# touch_pot_v13.net
KiCad netlist of a schematic drawn in EAGLE
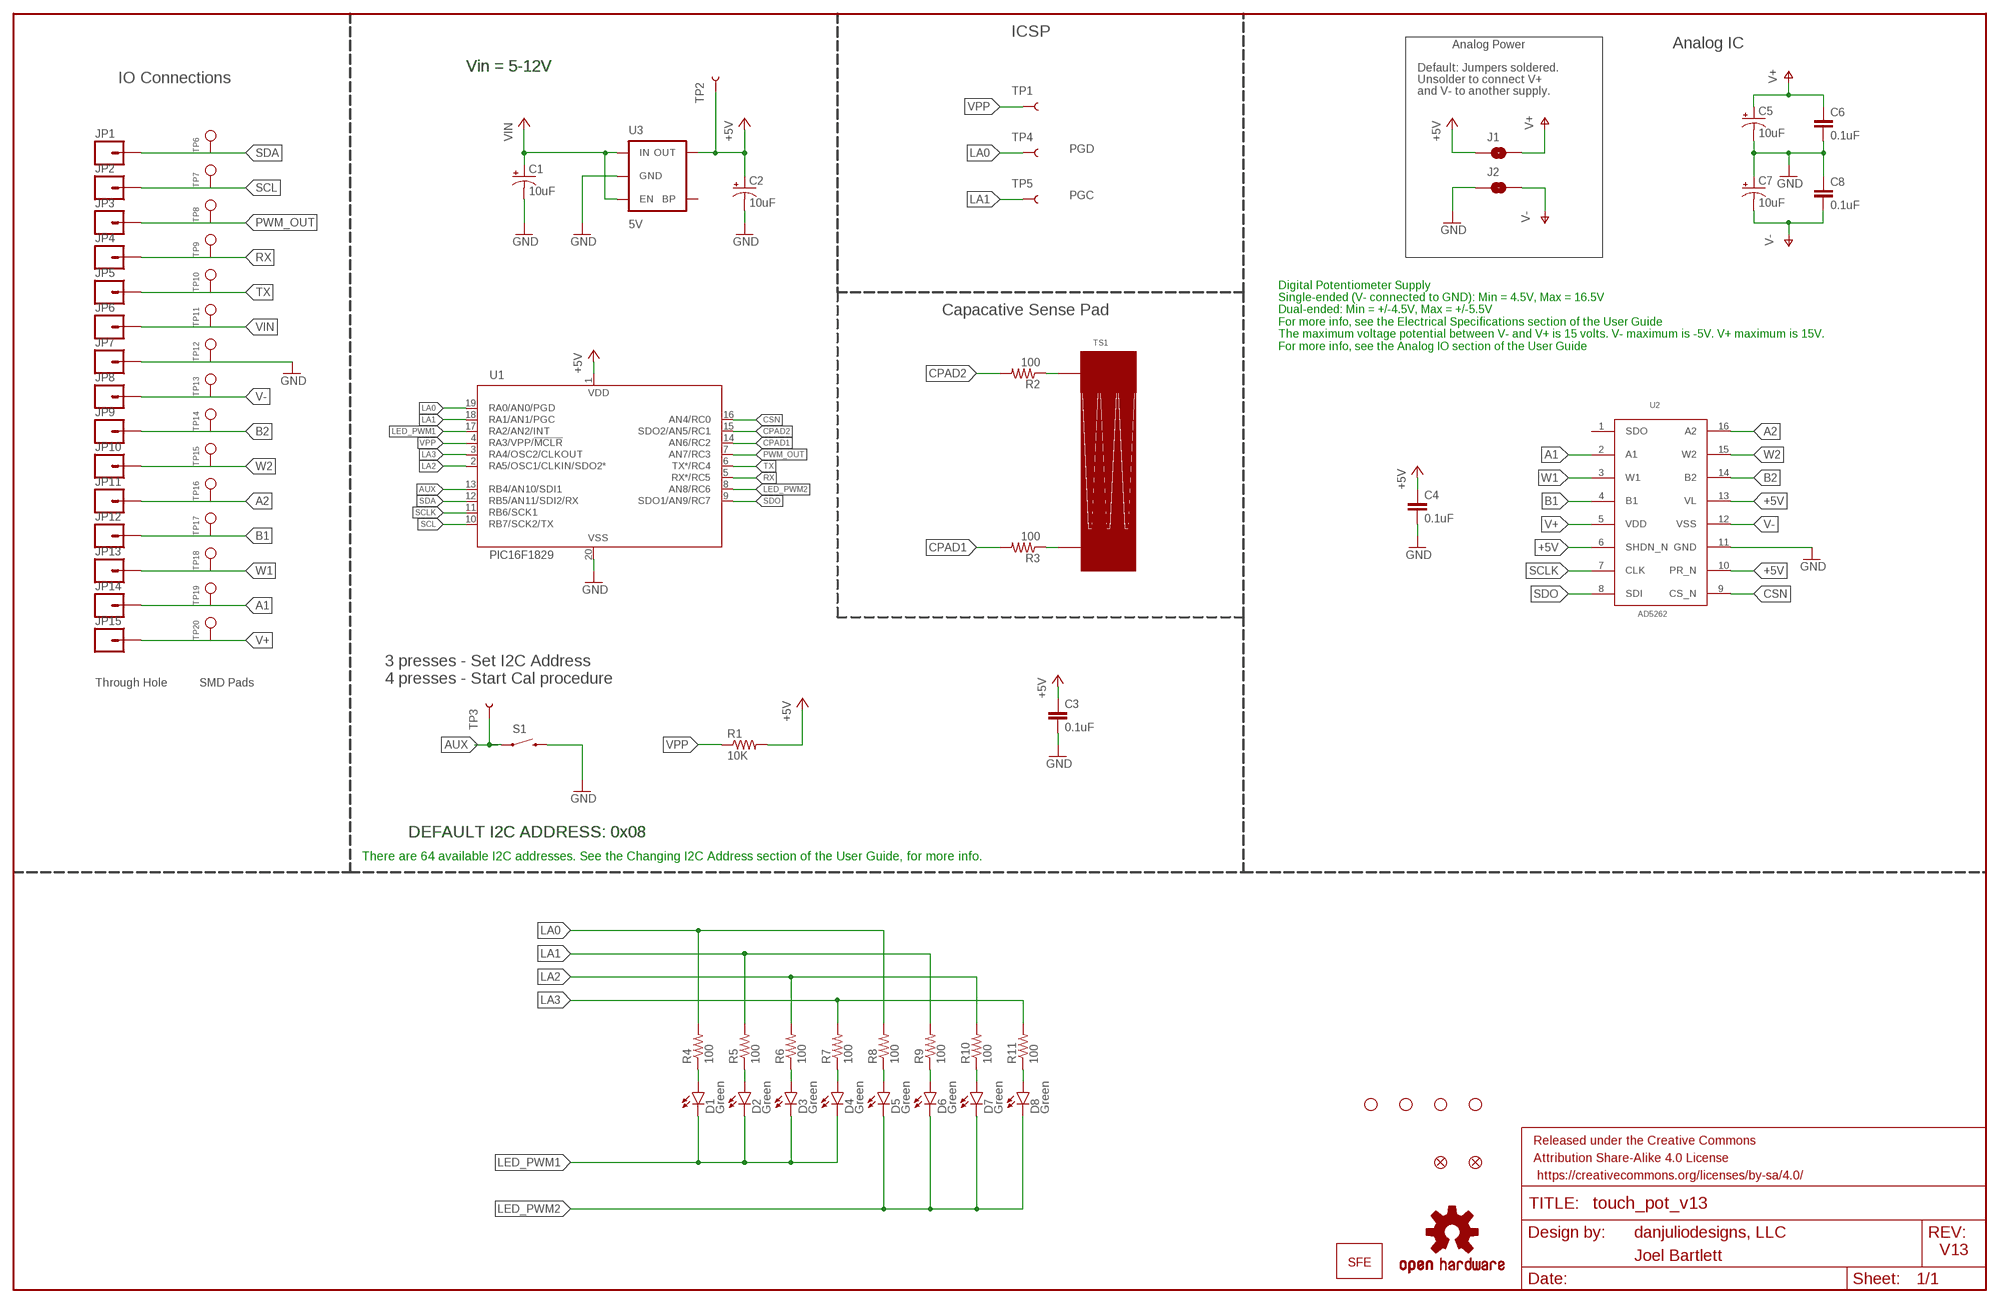
[diagram p0: schematic, sheet 1]

(export (version "E")
  (design (tool "Eeschema 10.0.6"))
  (components
    (comp (ref "C1")
      (value "10uF")
      (footprint "eagle-import:EIA3216")
      (libsource (lib "eagle-import") (part "10UF-16V-10%(TANT)"))
    )
    (comp (ref "C2")
      (value "10uF")
      (footprint "eagle-import:EIA3216")
      (libsource (lib "eagle-import") (part "10UF-16V-10%(TANT)"))
    )
    (comp (ref "C3")
      (value "0.1uF")
      (footprint "eagle-import:0603-CAP")
      (libsource (lib "eagle-import") (part "0.1UF-25V(+80/-20%)(0603)"))
    )
    (comp (ref "C4")
      (value "0.1uF")
      (footprint "eagle-import:0603-CAP")
      (libsource (lib "eagle-import") (part "0.1UF-25V(+80/-20%)(0603)"))
    )
    (comp (ref "C5")
      (value "10uF")
      (footprint "eagle-import:EIA3216")
      (libsource (lib "eagle-import") (part "10UF-16V-10%(TANT)"))
    )
    (comp (ref "C6")
      (value "0.1uF")
      (footprint "eagle-import:0603-CAP")
      (libsource (lib "eagle-import") (part "0.1UF-25V(+80/-20%)(0603)"))
    )
    (comp (ref "C7")
      (value "10uF")
      (footprint "eagle-import:EIA3216")
      (libsource (lib "eagle-import") (part "10UF-16V-10%(TANT)"))
    )
    (comp (ref "C8")
      (value "0.1uF")
      (footprint "eagle-import:0603-CAP")
      (libsource (lib "eagle-import") (part "0.1UF-25V(+80/-20%)(0603)"))
    )
    (comp (ref "D1")
      (value "Green")
      (footprint "eagle-import:LED-1206-BOTTOM")
      (libsource (lib "eagle-import") (part "LED-GREEN1206-BOTTOM"))
    )
    (comp (ref "D2")
      (value "Green")
      (footprint "eagle-import:LED-1206-BOTTOM")
      (libsource (lib "eagle-import") (part "LED-GREEN1206-BOTTOM"))
    )
    (comp (ref "D3")
      (value "Green")
      (footprint "eagle-import:LED-1206-BOTTOM")
      (libsource (lib "eagle-import") (part "LED-GREEN1206-BOTTOM"))
    )
    (comp (ref "D4")
      (value "Green")
      (footprint "eagle-import:LED-1206-BOTTOM")
      (libsource (lib "eagle-import") (part "LED-GREEN1206-BOTTOM"))
    )
    (comp (ref "D5")
      (value "Green")
      (footprint "eagle-import:LED-1206-BOTTOM")
      (libsource (lib "eagle-import") (part "LED-GREEN1206-BOTTOM"))
    )
    (comp (ref "D6")
      (value "Green")
      (footprint "eagle-import:LED-1206-BOTTOM")
      (libsource (lib "eagle-import") (part "LED-GREEN1206-BOTTOM"))
    )
    (comp (ref "D7")
      (value "Green")
      (footprint "eagle-import:LED-1206-BOTTOM")
      (libsource (lib "eagle-import") (part "LED-GREEN1206-BOTTOM"))
    )
    (comp (ref "D8")
      (value "Green")
      (footprint "eagle-import:LED-1206-BOTTOM")
      (libsource (lib "eagle-import") (part "LED-GREEN1206-BOTTOM"))
    )
    (comp (ref "FID1")
      (value "FIDUCIAL1X2")
      (footprint "eagle-import:FIDUCIAL-1X2")
      (libsource (lib "eagle-import") (part "FIDUCIAL1X2"))
    )
    (comp (ref "FID2")
      (value "FIDUCIAL1X2")
      (footprint "eagle-import:FIDUCIAL-1X2")
      (libsource (lib "eagle-import") (part "FIDUCIAL1X2"))
    )
    (comp (ref "FRAME3")
      (value "FRAME-LEDGER")
      (footprint "eagle-import:CREATIVE_COMMONS")
      (libsource (lib "eagle-import") (part "FRAME-LEDGER"))
    )
    (comp (ref "J1")
      (value "SJCLOSED")
      (footprint "eagle-import:SJ_2S")
      (libsource (lib "eagle-import") (part "SJCLOSED"))
    )
    (comp (ref "J2")
      (value "SJCLOSED")
      (footprint "eagle-import:SJ_2S")
      (libsource (lib "eagle-import") (part "SJCLOSED"))
    )
    (comp (ref "JP1")
      (value "M01SMDNS")
      (footprint "eagle-import:1X01NS")
      (libsource (lib "eagle-import") (part "M01SMDNS"))
    )
    (comp (ref "JP2")
      (value "M01SMDNS")
      (footprint "eagle-import:1X01NS")
      (libsource (lib "eagle-import") (part "M01SMDNS"))
    )
    (comp (ref "JP3")
      (value "M01SMDNS")
      (footprint "eagle-import:1X01NS")
      (libsource (lib "eagle-import") (part "M01SMDNS"))
    )
    (comp (ref "JP4")
      (value "M01SMDNS")
      (footprint "eagle-import:1X01NS")
      (libsource (lib "eagle-import") (part "M01SMDNS"))
    )
    (comp (ref "JP5")
      (value "M01SMDNS")
      (footprint "eagle-import:1X01NS")
      (libsource (lib "eagle-import") (part "M01SMDNS"))
    )
    (comp (ref "JP6")
      (value "M01SMDNS")
      (footprint "eagle-import:1X01NS")
      (libsource (lib "eagle-import") (part "M01SMDNS"))
    )
    (comp (ref "JP7")
      (value "M01SMDNS")
      (footprint "eagle-import:1X01NS")
      (libsource (lib "eagle-import") (part "M01SMDNS"))
    )
    (comp (ref "JP8")
      (value "M01SMDNS")
      (footprint "eagle-import:1X01NS")
      (libsource (lib "eagle-import") (part "M01SMDNS"))
    )
    (comp (ref "JP9")
      (value "M01SMDNS")
      (footprint "eagle-import:1X01NS")
      (libsource (lib "eagle-import") (part "M01SMDNS"))
    )
    (comp (ref "JP10")
      (value "M01SMDNS")
      (footprint "eagle-import:1X01NS")
      (libsource (lib "eagle-import") (part "M01SMDNS"))
    )
    (comp (ref "JP11")
      (value "M01SMDNS")
      (footprint "eagle-import:1X01NS")
      (libsource (lib "eagle-import") (part "M01SMDNS"))
    )
    (comp (ref "JP12")
      (value "M01SMDNS")
      (footprint "eagle-import:1X01NS")
      (libsource (lib "eagle-import") (part "M01SMDNS"))
    )
    (comp (ref "JP13")
      (value "M01SMDNS")
      (footprint "eagle-import:1X01NS")
      (libsource (lib "eagle-import") (part "M01SMDNS"))
    )
    (comp (ref "JP14")
      (value "M01SMDNS")
      (footprint "eagle-import:1X01NS")
      (libsource (lib "eagle-import") (part "M01SMDNS"))
    )
    (comp (ref "JP15")
      (value "M01SMDNS")
      (footprint "eagle-import:1X01NS")
      (libsource (lib "eagle-import") (part "M01SMDNS"))
    )
    (comp (ref "R1")
      (value "10K")
      (footprint "eagle-import:0603-RES")
      (libsource (lib "eagle-import") (part "10KOHM-1/10W-1%(0603)0603"))
    )
    (comp (ref "R2")
      (value "100")
      (footprint "eagle-import:0603-RES")
      (libsource (lib "eagle-import") (part "100OHM-1/10W-1%(0603)"))
    )
    (comp (ref "R3")
      (value "100")
      (footprint "eagle-import:0603-RES")
      (libsource (lib "eagle-import") (part "100OHM-1/10W-1%(0603)"))
    )
    (comp (ref "R4")
      (value "100")
      (footprint "eagle-import:0603-RES")
      (libsource (lib "eagle-import") (part "100OHM-1/10W-1%(0603)"))
    )
    (comp (ref "R5")
      (value "100")
      (footprint "eagle-import:0603-RES")
      (libsource (lib "eagle-import") (part "100OHM-1/10W-1%(0603)"))
    )
    (comp (ref "R6")
      (value "100")
      (footprint "eagle-import:0603-RES")
      (libsource (lib "eagle-import") (part "100OHM-1/10W-1%(0603)"))
    )
    (comp (ref "R7")
      (value "100")
      (footprint "eagle-import:0603-RES")
      (libsource (lib "eagle-import") (part "100OHM-1/10W-1%(0603)"))
    )
    (comp (ref "R8")
      (value "100")
      (footprint "eagle-import:0603-RES")
      (libsource (lib "eagle-import") (part "100OHM-1/10W-1%(0603)"))
    )
    (comp (ref "R9")
      (value "100")
      (footprint "eagle-import:0603-RES")
      (libsource (lib "eagle-import") (part "100OHM-1/10W-1%(0603)"))
    )
    (comp (ref "R10")
      (value "100")
      (footprint "eagle-import:0603-RES")
      (libsource (lib "eagle-import") (part "100OHM-1/10W-1%(0603)"))
    )
    (comp (ref "R11")
      (value "100")
      (footprint "eagle-import:0603-RES")
      (libsource (lib "eagle-import") (part "100OHM-1/10W-1%(0603)"))
    )
    (comp (ref "S1")
      (value "SWITCH-MOMENTARY-2SMD")
      (footprint "eagle-import:TACTILE-SWITCH-SMD")
      (libsource (lib "eagle-import") (part "SWITCH-MOMENTARY-2SMD"))
    )
    (comp (ref "STANDOFF1")
      (value "STAND-OFFTIGHT")
      (footprint "eagle-import:STAND-OFF-TIGHT")
      (libsource (lib "eagle-import") (part "STAND-OFFTIGHT"))
    )
    (comp (ref "STANDOFF2")
      (value "STAND-OFFTIGHT")
      (footprint "eagle-import:STAND-OFF-TIGHT")
      (libsource (lib "eagle-import") (part "STAND-OFFTIGHT"))
    )
    (comp (ref "STANDOFF3")
      (value "STAND-OFFTIGHT")
      (footprint "eagle-import:STAND-OFF-TIGHT")
      (libsource (lib "eagle-import") (part "STAND-OFFTIGHT"))
    )
    (comp (ref "STANDOFF4")
      (value "STAND-OFFTIGHT")
      (footprint "eagle-import:STAND-OFF-TIGHT")
      (libsource (lib "eagle-import") (part "STAND-OFFTIGHT"))
    )
    (comp (ref "TP1")
      (value "TEST-POINT3X4")
      (footprint "eagle-import:PAD.03X.04")
      (libsource (lib "eagle-import") (part "TEST-POINT3X4"))
    )
    (comp (ref "TP2")
      (value "TEST-POINT3X4")
      (footprint "eagle-import:PAD.03X.04")
      (libsource (lib "eagle-import") (part "TEST-POINT3X4"))
    )
    (comp (ref "TP3")
      (value "TEST-POINT3X4")
      (footprint "eagle-import:PAD.03X.04")
      (libsource (lib "eagle-import") (part "TEST-POINT3X4"))
    )
    (comp (ref "TP4")
      (value "TEST-POINT3X4")
      (footprint "eagle-import:PAD.03X.04")
      (libsource (lib "eagle-import") (part "TEST-POINT3X4"))
    )
    (comp (ref "TP5")
      (value "TEST-POINT3X4")
      (footprint "eagle-import:PAD.03X.04")
      (libsource (lib "eagle-import") (part "TEST-POINT3X4"))
    )
    (comp (ref "TP6")
      (value "SINGLE_PADSMD")
      (footprint "eagle-import:2MM_SMD_PAD")
      (libsource (lib "eagle-import") (part "SINGLE_PADSMD"))
    )
    (comp (ref "TP7")
      (value "SINGLE_PADSMD")
      (footprint "eagle-import:2MM_SMD_PAD")
      (libsource (lib "eagle-import") (part "SINGLE_PADSMD"))
    )
    (comp (ref "TP8")
      (value "SINGLE_PADSMD")
      (footprint "eagle-import:2MM_SMD_PAD")
      (libsource (lib "eagle-import") (part "SINGLE_PADSMD"))
    )
    (comp (ref "TP9")
      (value "SINGLE_PADSMD")
      (footprint "eagle-import:2MM_SMD_PAD")
      (libsource (lib "eagle-import") (part "SINGLE_PADSMD"))
    )
    (comp (ref "TP10")
      (value "SINGLE_PADSMD")
      (footprint "eagle-import:2MM_SMD_PAD")
      (libsource (lib "eagle-import") (part "SINGLE_PADSMD"))
    )
    (comp (ref "TP11")
      (value "SINGLE_PADSMD")
      (footprint "eagle-import:2MM_SMD_PAD")
      (libsource (lib "eagle-import") (part "SINGLE_PADSMD"))
    )
    (comp (ref "TP12")
      (value "SINGLE_PADSMD")
      (footprint "eagle-import:2MM_SMD_PAD")
      (libsource (lib "eagle-import") (part "SINGLE_PADSMD"))
    )
    (comp (ref "TP13")
      (value "SINGLE_PADSMD")
      (footprint "eagle-import:2MM_SMD_PAD")
      (libsource (lib "eagle-import") (part "SINGLE_PADSMD"))
    )
    (comp (ref "TP14")
      (value "SINGLE_PADSMD")
      (footprint "eagle-import:2MM_SMD_PAD")
      (libsource (lib "eagle-import") (part "SINGLE_PADSMD"))
    )
    (comp (ref "TP15")
      (value "SINGLE_PADSMD")
      (footprint "eagle-import:2MM_SMD_PAD")
      (libsource (lib "eagle-import") (part "SINGLE_PADSMD"))
    )
    (comp (ref "TP16")
      (value "SINGLE_PADSMD")
      (footprint "eagle-import:2MM_SMD_PAD")
      (libsource (lib "eagle-import") (part "SINGLE_PADSMD"))
    )
    (comp (ref "TP17")
      (value "SINGLE_PADSMD")
      (footprint "eagle-import:2MM_SMD_PAD")
      (libsource (lib "eagle-import") (part "SINGLE_PADSMD"))
    )
    (comp (ref "TP18")
      (value "SINGLE_PADSMD")
      (footprint "eagle-import:2MM_SMD_PAD")
      (libsource (lib "eagle-import") (part "SINGLE_PADSMD"))
    )
    (comp (ref "TP19")
      (value "SINGLE_PADSMD")
      (footprint "eagle-import:2MM_SMD_PAD")
      (libsource (lib "eagle-import") (part "SINGLE_PADSMD"))
    )
    (comp (ref "TP20")
      (value "SINGLE_PADSMD")
      (footprint "eagle-import:2MM_SMD_PAD")
      (libsource (lib "eagle-import") (part "SINGLE_PADSMD"))
    )
    (comp (ref "TS1")
      (value "2CH_LINEAR_TOUCH")
      (footprint "eagle-import:2CH_48MM_LINEAR_TOUCH")
      (libsource (lib "eagle-import") (part "2CH_LINEAR_TOUCH"))
    )
    (comp (ref "U$4")
      (value "OSHW-LOGOM")
      (footprint "eagle-import:OSHW-LOGO-M")
      (libsource (lib "eagle-import") (part "OSHW-LOGOM"))
    )
    (comp (ref "U$5")
      (value "SFE_LOGO_NAME_WEB")
      (footprint "eagle-import:SFE-NEW-WEBLOGO")
      (libsource (lib "eagle-import") (part "SFE_LOGO_NAME_WEB"))
    )
    (comp (ref "U1")
      (value "PIC16F1829")
      (footprint "eagle-import:SSOP20")
      (libsource (lib "eagle-import") (part "PIC16F1829"))
    )
    (comp (ref "U2")
      (value "AD5262")
      (footprint "eagle-import:SSOP16")
      (libsource (lib "eagle-import") (part "AD5262"))
    )
    (comp (ref "U3")
      (value "5V")
      (footprint "eagle-import:SOT23-5")
      (libsource (lib "eagle-import") (part "V_REG_MIC52055V"))
    )
  )
  (nets
    (net (code "1") (name "+5V") (class "Default")
      (node (ref "C2") (pin "A") (pinfunction "+_A") (pintype "passive"))
      (node (ref "C3") (pin "1") (pinfunction "1_1") (pintype "passive"))
      (node (ref "C4") (pin "1") (pinfunction "1_1") (pintype "passive"))
      (node (ref "J1") (pin "1") (pinfunction "1_1") (pintype "passive"))
      (node (ref "R1") (pin "2") (pinfunction "2_2") (pintype "passive"))
      (node (ref "TP2") (pin "P$1") (pinfunction "1_P$1") (pintype "bidirectional"))
      (node (ref "U1") (pin "1") (pinfunction "VDD_1") (pintype "power_in"))
      (node (ref "U2") (pin "10") (pinfunction "PR_N_10") (pintype "input"))
      (node (ref "U2") (pin "13") (pinfunction "VL_13") (pintype "power_in"))
      (node (ref "U2") (pin "6") (pinfunction "SHDN_N_6") (pintype "input"))
      (node (ref "U3") (pin "5") (pinfunction "OUT_5") (pintype "passive"))
    )
    (net (code "2") (name "A1") (class "Default")
      (node (ref "JP14") (pin "1") (pinfunction "1_1") (pintype "passive"))
      (node (ref "TP19") (pin "P$1") (pinfunction "P$1_P$1") (pintype "passive"))
      (node (ref "U2") (pin "2") (pinfunction "A1_2") (pintype "passive"))
    )
    (net (code "3") (name "A2") (class "Default")
      (node (ref "JP11") (pin "1") (pinfunction "1_1") (pintype "passive"))
      (node (ref "TP16") (pin "P$1") (pinfunction "P$1_P$1") (pintype "passive"))
      (node (ref "U2") (pin "16") (pinfunction "A2_16") (pintype "passive"))
    )
    (net (code "4") (name "AUX") (class "Default")
      (node (ref "S1") (pin "1") (pinfunction "1_1") (pintype "passive"))
      (node (ref "TP3") (pin "P$1") (pinfunction "1_P$1") (pintype "bidirectional"))
      (node (ref "U1") (pin "13") (pinfunction "RB4/AN10/SDI1_13") (pintype "bidirectional"))
    )
    (net (code "5") (name "B1") (class "Default")
      (node (ref "JP12") (pin "1") (pinfunction "1_1") (pintype "passive"))
      (node (ref "TP17") (pin "P$1") (pinfunction "P$1_P$1") (pintype "passive"))
      (node (ref "U2") (pin "4") (pinfunction "B1_4") (pintype "passive"))
    )
    (net (code "6") (name "B2") (class "Default")
      (node (ref "JP9") (pin "1") (pinfunction "1_1") (pintype "passive"))
      (node (ref "TP14") (pin "P$1") (pinfunction "P$1_P$1") (pintype "passive"))
      (node (ref "U2") (pin "14") (pinfunction "B2_14") (pintype "passive"))
    )
    (net (code "7") (name "CPAD1") (class "Default")
      (node (ref "R3") (pin "2") (pinfunction "2_2") (pintype "passive"))
      (node (ref "U1") (pin "14") (pinfunction "AN6/RC2_14") (pintype "bidirectional"))
    )
    (net (code "8") (name "CPAD2") (class "Default")
      (node (ref "R2") (pin "2") (pinfunction "2_2") (pintype "passive"))
      (node (ref "U1") (pin "15") (pinfunction "SDO2/AN5/RC1_15") (pintype "bidirectional"))
    )
    (net (code "9") (name "CSN") (class "Default")
      (node (ref "U1") (pin "16") (pinfunction "AN4/RC0_16") (pintype "bidirectional"))
      (node (ref "U2") (pin "9") (pinfunction "CS_N_9") (pintype "input"))
    )
    (net (code "10") (name "GND") (class "Default")
      (node (ref "C1") (pin "C") (pinfunction "-_C") (pintype "passive"))
      (node (ref "C2") (pin "C") (pinfunction "-_C") (pintype "passive"))
      (node (ref "C3") (pin "2") (pinfunction "2_2") (pintype "passive"))
      (node (ref "C4") (pin "2") (pinfunction "2_2") (pintype "passive"))
      (node (ref "C5") (pin "C") (pinfunction "-_C") (pintype "passive"))
      (node (ref "C6") (pin "2") (pinfunction "2_2") (pintype "passive"))
      (node (ref "C7") (pin "A") (pinfunction "+_A") (pintype "passive"))
      (node (ref "C8") (pin "1") (pinfunction "1_1") (pintype "passive"))
      (node (ref "J2") (pin "1") (pinfunction "1_1") (pintype "passive"))
      (node (ref "JP7") (pin "1") (pinfunction "1_1") (pintype "passive"))
      (node (ref "S1") (pin "3") (pinfunction "2_3") (pintype "passive"))
      (node (ref "TP12") (pin "P$1") (pinfunction "P$1_P$1") (pintype "passive"))
      (node (ref "U1") (pin "20") (pinfunction "VSS_20") (pintype "power_in"))
      (node (ref "U2") (pin "11") (pinfunction "GND_11") (pintype "power_in"))
      (node (ref "U3") (pin "2") (pinfunction "GND_2") (pintype "input"))
    )
    (net (code "11") (name "LA0") (class "Default")
      (node (ref "R4") (pin "2") (pinfunction "2_2") (pintype "passive"))
      (node (ref "R8") (pin "2") (pinfunction "2_2") (pintype "passive"))
      (node (ref "TP4") (pin "P$1") (pinfunction "1_P$1") (pintype "bidirectional"))
      (node (ref "U1") (pin "19") (pinfunction "RA0/AN0/PGD_19") (pintype "bidirectional"))
    )
    (net (code "12") (name "LA1") (class "Default")
      (node (ref "R5") (pin "2") (pinfunction "2_2") (pintype "passive"))
      (node (ref "R9") (pin "2") (pinfunction "2_2") (pintype "passive"))
      (node (ref "TP5") (pin "P$1") (pinfunction "1_P$1") (pintype "bidirectional"))
      (node (ref "U1") (pin "18") (pinfunction "RA1/AN1/PGC_18") (pintype "bidirectional"))
    )
    (net (code "13") (name "LA2") (class "Default")
      (node (ref "R10") (pin "2") (pinfunction "2_2") (pintype "passive"))
      (node (ref "R6") (pin "2") (pinfunction "2_2") (pintype "passive"))
      (node (ref "U1") (pin "2") (pinfunction "RA5/OSC1/CLKIN/SDO2*_2") (pintype "bidirectional"))
    )
    (net (code "14") (name "LA3") (class "Default")
      (node (ref "R11") (pin "2") (pinfunction "2_2") (pintype "passive"))
      (node (ref "R7") (pin "2") (pinfunction "2_2") (pintype "passive"))
      (node (ref "U1") (pin "3") (pinfunction "RA4/OSC2/CLKOUT_3") (pintype "bidirectional"))
    )
    (net (code "15") (name "LED_PWM1") (class "Default")
      (node (ref "D1") (pin "C") (pinfunction "C_C") (pintype "passive"))
      (node (ref "D2") (pin "C") (pinfunction "C_C") (pintype "passive"))
      (node (ref "D3") (pin "C") (pinfunction "C_C") (pintype "passive"))
      (node (ref "D4") (pin "C") (pinfunction "C_C") (pintype "passive"))
      (node (ref "U1") (pin "17") (pinfunction "RA2/AN2/INT_17") (pintype "bidirectional"))
    )
    (net (code "16") (name "LED_PWM2") (class "Default")
      (node (ref "D5") (pin "C") (pinfunction "C_C") (pintype "passive"))
      (node (ref "D6") (pin "C") (pinfunction "C_C") (pintype "passive"))
      (node (ref "D7") (pin "C") (pinfunction "C_C") (pintype "passive"))
      (node (ref "D8") (pin "C") (pinfunction "C_C") (pintype "passive"))
      (node (ref "U1") (pin "8") (pinfunction "AN8/RC6_8") (pintype "bidirectional"))
    )
    (net (code "17") (name "Net-(D1-PadA)") (class "Default")
      (node (ref "D1") (pin "A") (pinfunction "A_A") (pintype "passive"))
      (node (ref "R4") (pin "1") (pinfunction "1_1") (pintype "passive"))
    )
    (net (code "18") (name "Net-(D2-PadA)") (class "Default")
      (node (ref "D2") (pin "A") (pinfunction "A_A") (pintype "passive"))
      (node (ref "R5") (pin "1") (pinfunction "1_1") (pintype "passive"))
    )
    (net (code "19") (name "Net-(D3-PadA)") (class "Default")
      (node (ref "D3") (pin "A") (pinfunction "A_A") (pintype "passive"))
      (node (ref "R6") (pin "1") (pinfunction "1_1") (pintype "passive"))
    )
    (net (code "20") (name "Net-(D4-PadA)") (class "Default")
      (node (ref "D4") (pin "A") (pinfunction "A_A") (pintype "passive"))
      (node (ref "R7") (pin "1") (pinfunction "1_1") (pintype "passive"))
    )
    (net (code "21") (name "Net-(D5-PadA)") (class "Default")
      (node (ref "D5") (pin "A") (pinfunction "A_A") (pintype "passive"))
      (node (ref "R8") (pin "1") (pinfunction "1_1") (pintype "passive"))
    )
    (net (code "22") (name "Net-(D6-PadA)") (class "Default")
      (node (ref "D6") (pin "A") (pinfunction "A_A") (pintype "passive"))
      (node (ref "R9") (pin "1") (pinfunction "1_1") (pintype "passive"))
    )
    (net (code "23") (name "Net-(D7-PadA)") (class "Default")
      (node (ref "D7") (pin "A") (pinfunction "A_A") (pintype "passive"))
      (node (ref "R10") (pin "1") (pinfunction "1_1") (pintype "passive"))
    )
    (net (code "24") (name "Net-(D8-PadA)") (class "Default")
      (node (ref "D8") (pin "A") (pinfunction "A_A") (pintype "passive"))
      (node (ref "R11") (pin "1") (pinfunction "1_1") (pintype "passive"))
    )
    (net (code "25") (name "Net-(R2-Pad1)") (class "Default")
      (node (ref "R2") (pin "1") (pinfunction "1_1") (pintype "passive"))
      (node (ref "TS1") (pin "P$2") (pinfunction "P$2_P$2") (pintype "bidirectional"))
    )
    (net (code "26") (name "Net-(R3-Pad1)") (class "Default")
      (node (ref "R3") (pin "1") (pinfunction "1_1") (pintype "passive"))
      (node (ref "TS1") (pin "P$1") (pinfunction "P$1_P$1") (pintype "bidirectional"))
    )
    (net (code "27") (name "PWM_OUT") (class "Default")
      (node (ref "JP3") (pin "1") (pinfunction "1_1") (pintype "passive"))
      (node (ref "TP8") (pin "P$1") (pinfunction "P$1_P$1") (pintype "passive"))
      (node (ref "U1") (pin "7") (pinfunction "AN7/RC3_7") (pintype "bidirectional"))
    )
    (net (code "28") (name "RX") (class "Default")
      (node (ref "JP4") (pin "1") (pinfunction "1_1") (pintype "passive"))
      (node (ref "TP9") (pin "P$1") (pinfunction "P$1_P$1") (pintype "passive"))
      (node (ref "U1") (pin "5") (pinfunction "RX*/RC5_5") (pintype "bidirectional"))
    )
    (net (code "29") (name "SCL") (class "Default")
      (node (ref "JP2") (pin "1") (pinfunction "1_1") (pintype "passive"))
      (node (ref "TP7") (pin "P$1") (pinfunction "P$1_P$1") (pintype "passive"))
      (node (ref "U1") (pin "10") (pinfunction "RB7/SCK2/TX_10") (pintype "bidirectional"))
    )
    (net (code "30") (name "SCLK") (class "Default")
      (node (ref "U1") (pin "11") (pinfunction "RB6/SCK1_11") (pintype "bidirectional"))
      (node (ref "U2") (pin "7") (pinfunction "CLK_7") (pintype "input"))
    )
    (net (code "31") (name "SDA") (class "Default")
      (node (ref "JP1") (pin "1") (pinfunction "1_1") (pintype "passive"))
      (node (ref "TP6") (pin "P$1") (pinfunction "P$1_P$1") (pintype "passive"))
      (node (ref "U1") (pin "12") (pinfunction "RB5/AN11/SDI2/RX_12") (pintype "bidirectional"))
    )
    (net (code "32") (name "SDO") (class "Default")
      (node (ref "U1") (pin "9") (pinfunction "SDO1/AN9/RC7_9") (pintype "bidirectional"))
      (node (ref "U2") (pin "8") (pinfunction "SDI_8") (pintype "input"))
    )
    (net (code "33") (name "TX") (class "Default")
      (node (ref "JP5") (pin "1") (pinfunction "1_1") (pintype "passive"))
      (node (ref "TP10") (pin "P$1") (pinfunction "P$1_P$1") (pintype "passive"))
      (node (ref "U1") (pin "6") (pinfunction "TX*/RC4_6") (pintype "bidirectional"))
    )
    (net (code "34") (name "V+") (class "Default")
      (node (ref "C5") (pin "A") (pinfunction "+_A") (pintype "passive"))
      (node (ref "C6") (pin "1") (pinfunction "1_1") (pintype "passive"))
      (node (ref "J1") (pin "2") (pinfunction "2_2") (pintype "passive"))
      (node (ref "JP15") (pin "1") (pinfunction "1_1") (pintype "passive"))
      (node (ref "TP20") (pin "P$1") (pinfunction "P$1_P$1") (pintype "passive"))
      (node (ref "U2") (pin "5") (pinfunction "VDD_5") (pintype "power_in"))
    )
    (net (code "35") (name "V-") (class "Default")
      (node (ref "C7") (pin "C") (pinfunction "-_C") (pintype "passive"))
      (node (ref "C8") (pin "2") (pinfunction "2_2") (pintype "passive"))
      (node (ref "J2") (pin "2") (pinfunction "2_2") (pintype "passive"))
      (node (ref "JP8") (pin "1") (pinfunction "1_1") (pintype "passive"))
      (node (ref "TP13") (pin "P$1") (pinfunction "P$1_P$1") (pintype "passive"))
      (node (ref "U2") (pin "12") (pinfunction "VSS_12") (pintype "power_in"))
    )
    (net (code "36") (name "VIN") (class "Default")
      (node (ref "C1") (pin "A") (pinfunction "+_A") (pintype "passive"))
      (node (ref "JP6") (pin "1") (pinfunction "1_1") (pintype "passive"))
      (node (ref "TP11") (pin "P$1") (pinfunction "P$1_P$1") (pintype "passive"))
      (node (ref "U3") (pin "1") (pinfunction "IN_1") (pintype "input"))
      (node (ref "U3") (pin "3") (pinfunction "EN_3") (pintype "input"))
    )
    (net (code "37") (name "VPP") (class "Default")
      (node (ref "R1") (pin "1") (pinfunction "1_1") (pintype "passive"))
      (node (ref "TP1") (pin "P$1") (pinfunction "1_P$1") (pintype "bidirectional"))
      (node (ref "U1") (pin "4") (pinfunction "RA3/VPP/~{MCLR}_4") (pintype "input"))
    )
    (net (code "38") (name "W1") (class "Default")
      (node (ref "JP13") (pin "1") (pinfunction "1_1") (pintype "passive"))
      (node (ref "TP18") (pin "P$1") (pinfunction "P$1_P$1") (pintype "passive"))
      (node (ref "U2") (pin "3") (pinfunction "W1_3") (pintype "passive"))
    )
    (net (code "39") (name "W2") (class "Default")
      (node (ref "JP10") (pin "1") (pinfunction "1_1") (pintype "passive"))
      (node (ref "TP15") (pin "P$1") (pinfunction "P$1_P$1") (pintype "passive"))
      (node (ref "U2") (pin "15") (pinfunction "W2_15") (pintype "passive"))
    )
    (net (code "40") (name "unconnected-(U2-SDO-Pad1)") (class "Default")
      (node (ref "U2") (pin "1") (pinfunction "SDO_1") (pintype "output"))
    )
    (net (code "41") (name "unconnected-(U3-BP-Pad4)") (class "Default")
      (node (ref "U3") (pin "4") (pinfunction "BP_4") (pintype "input"))
    )
  )
)
